# MP3_Breakout.net
KiCad netlist of a schematic drawn in EAGLE
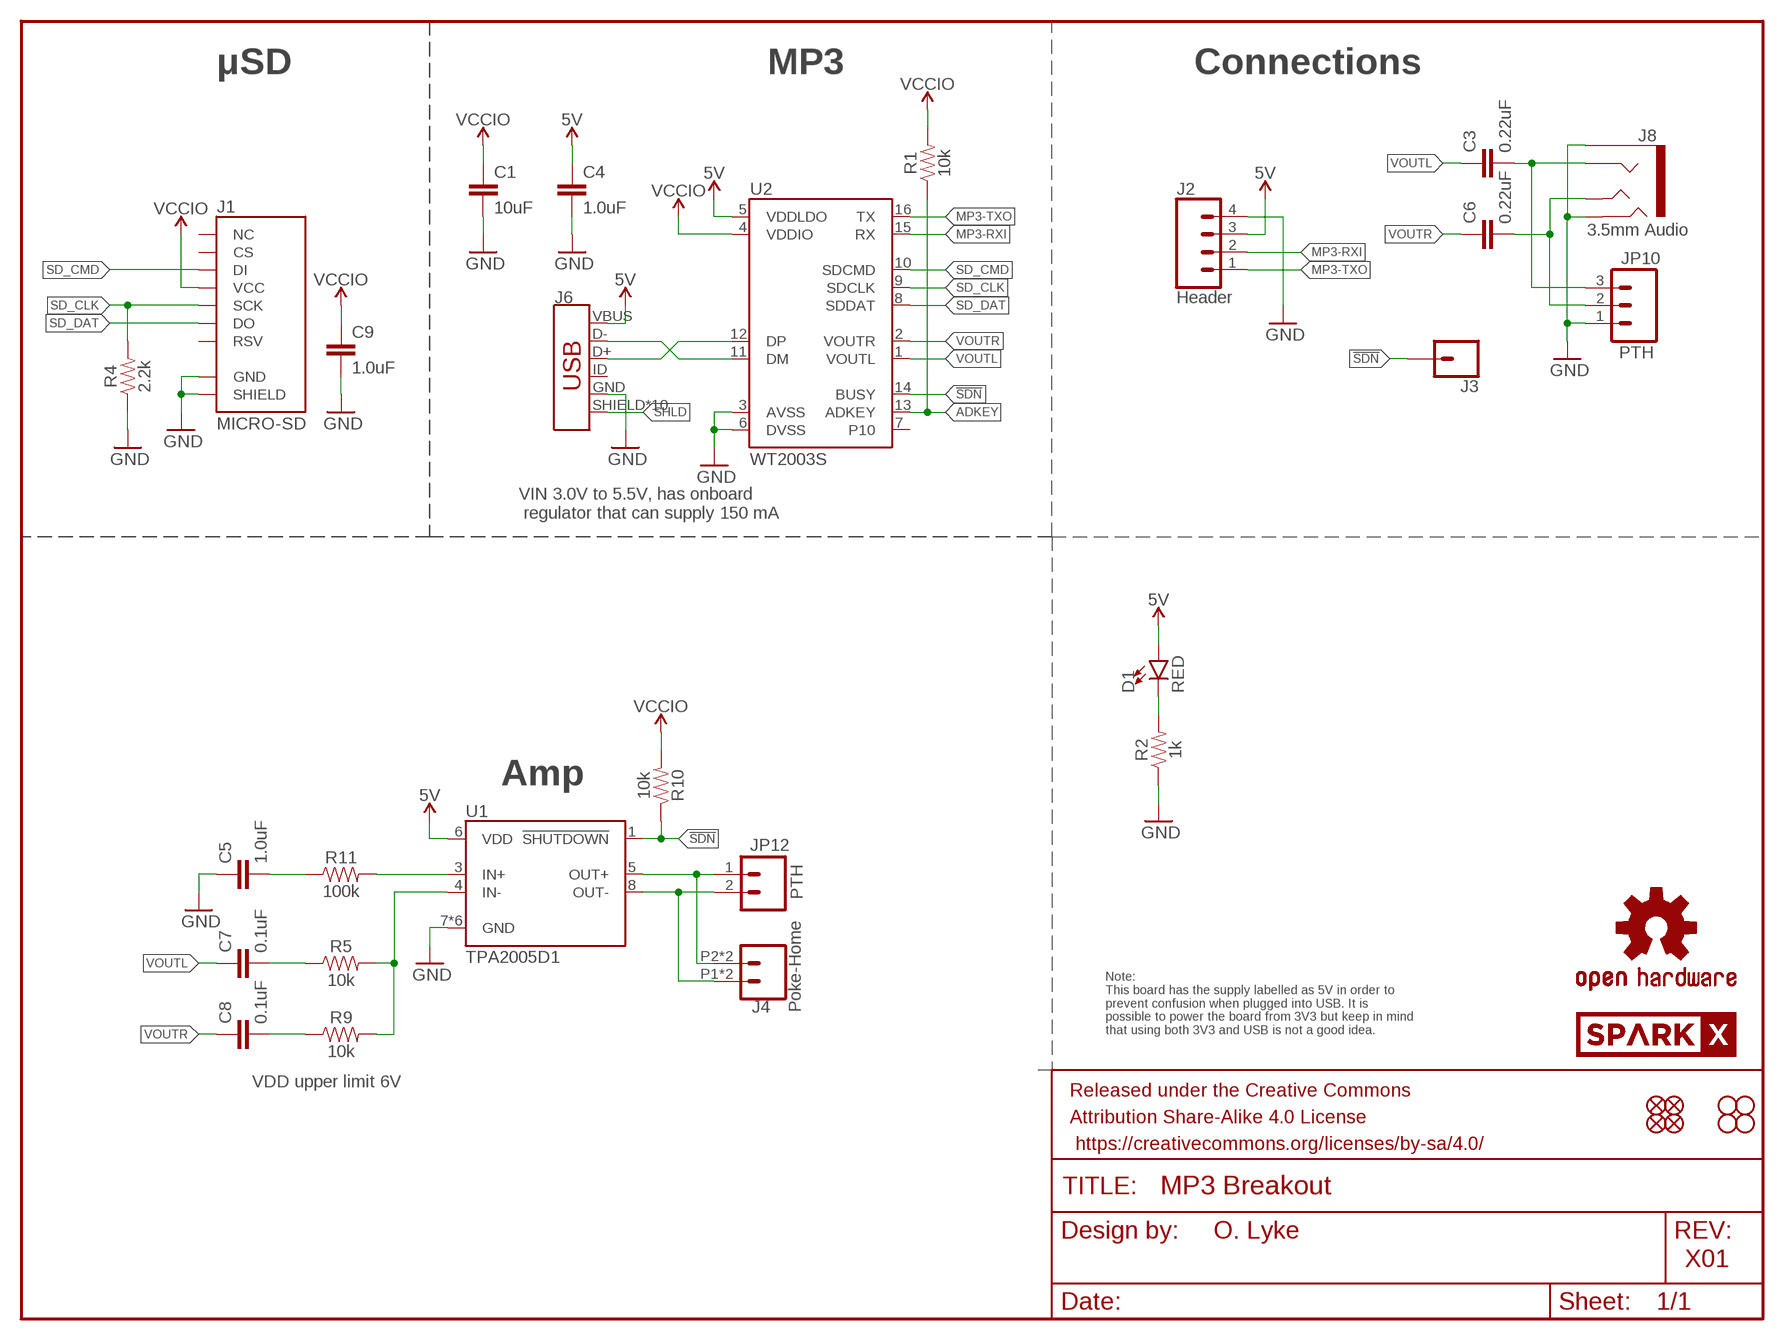
[diagram p0: schematic, sheet 1]

(export (version "E")
  (design (tool "Eeschema 10.0.6"))
  (components
    (comp (ref "C1")
      (value "10uF")
      (footprint "eagle-import:0603")
      (libsource (lib "eagle-import") (part "10UF-0603-6.3V-20%"))
    )
    (comp (ref "C3")
      (value "0.22uF")
      (footprint "eagle-import:0603")
      (libsource (lib "eagle-import") (part "0.22UF-0603-25V-10%"))
    )
    (comp (ref "C4")
      (value "1.0uF")
      (footprint "eagle-import:0603")
      (libsource (lib "eagle-import") (part "1.0UF-0603-16V-10%"))
    )
    (comp (ref "C5")
      (value "1.0uF")
      (footprint "eagle-import:0603")
      (libsource (lib "eagle-import") (part "1.0UF-0603-16V-10%"))
    )
    (comp (ref "C6")
      (value "0.22uF")
      (footprint "eagle-import:0603")
      (libsource (lib "eagle-import") (part "0.22UF-0603-25V-10%"))
    )
    (comp (ref "C7")
      (value "0.1uF")
      (footprint "eagle-import:0603")
      (libsource (lib "eagle-import") (part "0.1UF-0603-25V-(+80/-20%)"))
    )
    (comp (ref "C8")
      (value "0.1uF")
      (footprint "eagle-import:0603")
      (libsource (lib "eagle-import") (part "0.1UF-0603-25V-(+80/-20%)"))
    )
    (comp (ref "C9")
      (value "1.0uF")
      (footprint "eagle-import:0603")
      (libsource (lib "eagle-import") (part "1.0UF-0603-16V-10%"))
    )
    (comp (ref "D1")
      (value "RED")
      (footprint "eagle-import:LED-0603")
      (libsource (lib "eagle-import") (part "LED-RED0603"))
    )
    (comp (ref "FRAME1")
      (value "FRAME-LETTER")
      (footprint "eagle-import:CREATIVE_COMMONS")
      (libsource (lib "eagle-import") (part "FRAME-LETTER"))
    )
    (comp (ref "J1")
      (value "MICRO-SD")
      (footprint "eagle-import:MICRO-SD-SOCKET")
      (libsource (lib "eagle-import") (part "MICRO-SD_CARD_SOCKETPUSH-PUSH"))
    )
    (comp (ref "J2")
      (value "Header")
      (footprint "eagle-import:1X04_NO_SILK")
      (libsource (lib "eagle-import") (part "CONN_041X04_NO_SILK"))
    )
    (comp (ref "J3")
      (value "CONN_01PTH_NO_SILK_YES_STOP")
      (footprint "eagle-import:1X01_NO_SILK")
      (libsource (lib "eagle-import") (part "CONN_01PTH_NO_SILK_YES_STOP"))
    )
    (comp (ref "J4")
      (value "Poke-Home")
      (footprint "eagle-import:1X02_POKEHOME")
      (libsource (lib "eagle-import") (part "CONN_02SMALL_POKEHOME"))
    )
    (comp (ref "J6")
      (value "USB_MICRO-B_HALF_PTH_MILL")
      (footprint "eagle-import:USB-MICROB-PTH-MILL")
      (libsource (lib "eagle-import") (part "USB_MICRO-B_HALF_PTH_MILL"))
    )
    (comp (ref "J8")
      (value "3.5mm Audio")
      (footprint "eagle-import:AUDIO_JACK_3.5MM_TRRS_SMD_RA")
      (libsource (lib "eagle-import") (part "AUDIO_JACK_TRRSSMD_RA"))
    )
    (comp (ref "JP1")
      (value "FIDUCIALUFIDUCIAL")
      (footprint "eagle-import:MICRO-FIDUCIAL")
      (libsource (lib "eagle-import") (part "FIDUCIALUFIDUCIAL"))
    )
    (comp (ref "JP2")
      (value "FIDUCIALUFIDUCIAL")
      (footprint "eagle-import:MICRO-FIDUCIAL")
      (libsource (lib "eagle-import") (part "FIDUCIALUFIDUCIAL"))
    )
    (comp (ref "JP3")
      (value "STAND-OFF")
      (footprint "eagle-import:STAND-OFF")
      (libsource (lib "eagle-import") (part "STAND-OFF"))
    )
    (comp (ref "JP4")
      (value "STAND-OFF")
      (footprint "eagle-import:STAND-OFF")
      (libsource (lib "eagle-import") (part "STAND-OFF"))
    )
    (comp (ref "JP5")
      (value "FIDUCIALUFIDUCIAL")
      (footprint "eagle-import:MICRO-FIDUCIAL")
      (libsource (lib "eagle-import") (part "FIDUCIALUFIDUCIAL"))
    )
    (comp (ref "JP6")
      (value "FIDUCIALUFIDUCIAL")
      (footprint "eagle-import:MICRO-FIDUCIAL")
      (libsource (lib "eagle-import") (part "FIDUCIALUFIDUCIAL"))
    )
    (comp (ref "JP10")
      (value "PTH")
      (footprint "eagle-import:1X03_NO_SILK")
      (libsource (lib "eagle-import") (part "CONN_031X03_NO_SILK"))
    )
    (comp (ref "JP11")
      (value "STAND-OFF")
      (footprint "eagle-import:STAND-OFF")
      (libsource (lib "eagle-import") (part "STAND-OFF"))
    )
    (comp (ref "JP12")
      (value "PTH")
      (footprint "eagle-import:1X02_NO_SILK")
      (libsource (lib "eagle-import") (part "CONN_021X02_NO_SILK"))
    )
    (comp (ref "JP13")
      (value "STAND-OFF")
      (footprint "eagle-import:STAND-OFF")
      (libsource (lib "eagle-import") (part "STAND-OFF"))
    )
    (comp (ref "LOGO1")
      (value "OSHW-LOGOMINI")
      (footprint "eagle-import:OSHW-LOGO-MINI")
      (libsource (lib "eagle-import") (part "OSHW-LOGOMINI"))
    )
    (comp (ref "R1")
      (value "10k")
      (footprint "eagle-import:0603")
      (libsource (lib "eagle-import") (part "10KOHM-0603-1/10W-1%"))
    )
    (comp (ref "R2")
      (value "1k")
      (footprint "eagle-import:0603")
      (libsource (lib "eagle-import") (part "1KOHM-0603-1/10W-1%"))
    )
    (comp (ref "R4")
      (value "2.2k")
      (footprint "eagle-import:0603")
      (libsource (lib "eagle-import") (part "2.2KOHM-0603-1/10W-1%"))
    )
    (comp (ref "R5")
      (value "10k")
      (footprint "eagle-import:0603")
      (libsource (lib "eagle-import") (part "10KOHM-0603-1/10W-1%"))
    )
    (comp (ref "R9")
      (value "10k")
      (footprint "eagle-import:0603")
      (libsource (lib "eagle-import") (part "10KOHM-0603-1/10W-1%"))
    )
    (comp (ref "R10")
      (value "10k")
      (footprint "eagle-import:0603")
      (libsource (lib "eagle-import") (part "10KOHM-0603-1/10W-1%"))
    )
    (comp (ref "R11")
      (value "100k")
      (footprint "eagle-import:0603")
      (libsource (lib "eagle-import") (part "100KOHM-0603-1/10W-1%"))
    )
    (comp (ref "U$2")
      (value "SPARKX-LOGO4")
      (footprint "eagle-import:SPARKX-MEDIUM")
      (libsource (lib "eagle-import") (part "SPARKX-LOGO4"))
    )
    (comp (ref "U1")
      (value "TPA2005D1")
      (footprint "eagle-import:QFN-8_PAD")
      (libsource (lib "eagle-import") (part "TPA2005D1DRB"))
    )
    (comp (ref "U2")
      (value "WT2003S")
      (footprint "eagle-import:SO16")
      (libsource (lib "eagle-import") (part "WT2003S"))
    )
  )
  (nets
    (net (code "1") (name "/~{SDN}") (class "Default")
      (node (ref "J3") (pin "1") (pinfunction "1_1") (pintype "passive"))
      (node (ref "R10") (pin "1") (pinfunction "1_1") (pintype "passive"))
      (node (ref "U1") (pin "1") (pinfunction "~{SHUTDOWN}_1") (pintype "input"))
      (node (ref "U2") (pin "14") (pinfunction "BUSY_14") (pintype "bidirectional"))
    )
    (net (code "2") (name "5V") (class "Default")
      (node (ref "C4") (pin "1") (pinfunction "1_1") (pintype "passive"))
      (node (ref "D1") (pin "A") (pinfunction "A_A") (pintype "passive"))
      (node (ref "J2") (pin "3") (pinfunction "3_3") (pintype "passive"))
      (node (ref "J6") (pin "VBUS") (pinfunction "VBUS_VBUS") (pintype "power_in"))
      (node (ref "U1") (pin "6") (pinfunction "VDD_6") (pintype "power_in"))
      (node (ref "U2") (pin "5") (pinfunction "VDDLDO_5") (pintype "bidirectional"))
    )
    (net (code "3") (name "ADKEY") (class "Default")
      (node (ref "R1") (pin "1") (pinfunction "1_1") (pintype "passive"))
      (node (ref "U2") (pin "13") (pinfunction "ADKEY_13") (pintype "bidirectional"))
    )
    (net (code "4") (name "GND") (class "Default")
      (node (ref "C1") (pin "2") (pinfunction "2_2") (pintype "passive"))
      (node (ref "C4") (pin "2") (pinfunction "2_2") (pintype "passive"))
      (node (ref "C5") (pin "1") (pinfunction "1_1") (pintype "passive"))
      (node (ref "C9") (pin "2") (pinfunction "2_2") (pintype "passive"))
      (node (ref "J1") (pin "CD1") (pinfunction "SHIELD_CD1") (pintype "bidirectional"))
      (node (ref "J1") (pin "GND") (pinfunction "GND_GND") (pintype "bidirectional"))
      (node (ref "J2") (pin "4") (pinfunction "4_4") (pintype "passive"))
      (node (ref "J6") (pin "GND") (pinfunction "GND_GND") (pintype "power_in"))
      (node (ref "J8") (pin "EARTH") (pinfunction "EARTH_EARTH") (pintype "bidirectional"))
      (node (ref "J8") (pin "RING2") (pinfunction "RING2_RING2") (pintype "bidirectional"))
      (node (ref "JP10") (pin "1") (pinfunction "1_1") (pintype "passive"))
      (node (ref "R2") (pin "1") (pinfunction "1_1") (pintype "passive"))
      (node (ref "R4") (pin "1") (pinfunction "1_1") (pintype "passive"))
      (node (ref "U1") (pin "10") (pinfunction "GND_10") (pintype "power_in"))
      (node (ref "U1") (pin "11") (pinfunction "GND_11") (pintype "power_in"))
      (node (ref "U1") (pin "12") (pinfunction "GND_12") (pintype "power_in"))
      (node (ref "U1") (pin "13") (pinfunction "GND_13") (pintype "power_in"))
      (node (ref "U1") (pin "7") (pinfunction "GND_7") (pintype "power_in"))
      (node (ref "U1") (pin "9") (pinfunction "GND_9") (pintype "power_in"))
      (node (ref "U2") (pin "3") (pinfunction "AVSS_3") (pintype "bidirectional"))
      (node (ref "U2") (pin "6") (pinfunction "DVSS_6") (pintype "bidirectional"))
    )
    (net (code "5") (name "MP3-RXI") (class "Default")
      (node (ref "J2") (pin "2") (pinfunction "2_2") (pintype "passive"))
      (node (ref "U2") (pin "15") (pinfunction "RX_15") (pintype "bidirectional"))
    )
    (net (code "6") (name "MP3-TXO") (class "Default")
      (node (ref "J2") (pin "1") (pinfunction "1_1") (pintype "passive"))
      (node (ref "U2") (pin "16") (pinfunction "TX_16") (pintype "bidirectional"))
    )
    (net (code "7") (name "Net-(C3-Pad2)") (class "Default")
      (node (ref "C3") (pin "2") (pinfunction "2_2") (pintype "passive"))
      (node (ref "J8") (pin "RING1") (pinfunction "RING1_RING1") (pintype "bidirectional"))
      (node (ref "JP10") (pin "3") (pinfunction "3_3") (pintype "passive"))
    )
    (net (code "8") (name "Net-(C5-Pad2)") (class "Default")
      (node (ref "C5") (pin "2") (pinfunction "2_2") (pintype "passive"))
      (node (ref "R11") (pin "1") (pinfunction "1_1") (pintype "passive"))
    )
    (net (code "9") (name "Net-(C6-Pad2)") (class "Default")
      (node (ref "C6") (pin "2") (pinfunction "2_2") (pintype "passive"))
      (node (ref "J8") (pin "TIP") (pinfunction "TIP_TIP") (pintype "bidirectional"))
      (node (ref "JP10") (pin "2") (pinfunction "2_2") (pintype "passive"))
    )
    (net (code "10") (name "Net-(C7-Pad2)") (class "Default")
      (node (ref "C7") (pin "2") (pinfunction "2_2") (pintype "passive"))
      (node (ref "R5") (pin "1") (pinfunction "1_1") (pintype "passive"))
    )
    (net (code "11") (name "Net-(C8-Pad2)") (class "Default")
      (node (ref "C8") (pin "2") (pinfunction "2_2") (pintype "passive"))
      (node (ref "R9") (pin "1") (pinfunction "1_1") (pintype "passive"))
    )
    (net (code "12") (name "Net-(D1-PadC)") (class "Default")
      (node (ref "D1") (pin "C") (pinfunction "C_C") (pintype "passive"))
      (node (ref "R2") (pin "2") (pinfunction "2_2") (pintype "passive"))
    )
    (net (code "13") (name "Net-(U1-IN+)") (class "Default")
      (node (ref "R11") (pin "2") (pinfunction "2_2") (pintype "passive"))
      (node (ref "U1") (pin "3") (pinfunction "IN+_3") (pintype "bidirectional"))
    )
    (net (code "14") (name "Net-(U1-IN-)") (class "Default")
      (node (ref "R5") (pin "2") (pinfunction "2_2") (pintype "passive"))
      (node (ref "R9") (pin "2") (pinfunction "2_2") (pintype "passive"))
      (node (ref "U1") (pin "4") (pinfunction "IN-_4") (pintype "bidirectional"))
    )
    (net (code "15") (name "Net-(U1-OUT+)") (class "Default")
      (node (ref "J4") (pin "P2") (pinfunction "2_P2") (pintype "passive"))
      (node (ref "J4") (pin "P4") (pinfunction "2_P4") (pintype "passive"))
      (node (ref "JP12") (pin "1") (pinfunction "1_1") (pintype "passive"))
      (node (ref "U1") (pin "5") (pinfunction "OUT+_5") (pintype "bidirectional"))
    )
    (net (code "16") (name "Net-(U1-OUT-)") (class "Default")
      (node (ref "J4") (pin "P1") (pinfunction "1_P1") (pintype "passive"))
      (node (ref "J4") (pin "P3") (pinfunction "1_P3") (pintype "passive"))
      (node (ref "JP12") (pin "2") (pinfunction "2_2") (pintype "passive"))
      (node (ref "U1") (pin "8") (pinfunction "OUT-_8") (pintype "bidirectional"))
    )
    (net (code "17") (name "Net-(U2-DM)") (class "Default")
      (node (ref "J6") (pin "D-") (pinfunction "D-_D-") (pintype "bidirectional"))
      (node (ref "U2") (pin "11") (pinfunction "DM_11") (pintype "bidirectional"))
    )
    (net (code "18") (name "Net-(U2-DP)") (class "Default")
      (node (ref "J6") (pin "D+") (pinfunction "D+_D+") (pintype "bidirectional"))
      (node (ref "U2") (pin "12") (pinfunction "DP_12") (pintype "bidirectional"))
    )
    (net (code "19") (name "SD_CLK") (class "Default")
      (node (ref "J1") (pin "SCLK") (pinfunction "SCK_SCLK") (pintype "bidirectional"))
      (node (ref "R4") (pin "2") (pinfunction "2_2") (pintype "passive"))
      (node (ref "U2") (pin "9") (pinfunction "SDCLK_9") (pintype "bidirectional"))
    )
    (net (code "20") (name "SD_CMD") (class "Default")
      (node (ref "J1") (pin "DI") (pinfunction "DI_DI") (pintype "bidirectional"))
      (node (ref "U2") (pin "10") (pinfunction "SDCMD_10") (pintype "bidirectional"))
    )
    (net (code "21") (name "SD_DAT") (class "Default")
      (node (ref "J1") (pin "DO") (pinfunction "DO_DO") (pintype "bidirectional"))
      (node (ref "U2") (pin "8") (pinfunction "SDDAT_8") (pintype "bidirectional"))
    )
    (net (code "22") (name "SHLD") (class "Default")
      (node (ref "J6") (pin "SHIELD") (pinfunction "SHIELD_SHIELD") (pintype "bidirectional"))
      (node (ref "J6") (pin "SHIELD10") (pinfunction "SHIELD_SHIELD10") (pintype "bidirectional"))
      (node (ref "J6") (pin "SHIELD2") (pinfunction "SHIELD_SHIELD2") (pintype "bidirectional"))
      (node (ref "J6") (pin "SHIELD3") (pinfunction "SHIELD_SHIELD3") (pintype "bidirectional"))
      (node (ref "J6") (pin "SHIELD4") (pinfunction "SHIELD_SHIELD4") (pintype "bidirectional"))
      (node (ref "J6") (pin "SHIELD5") (pinfunction "SHIELD_SHIELD5") (pintype "bidirectional"))
      (node (ref "J6") (pin "SHIELD6") (pinfunction "SHIELD_SHIELD6") (pintype "bidirectional"))
      (node (ref "J6") (pin "SHIELD7") (pinfunction "SHIELD_SHIELD7") (pintype "bidirectional"))
      (node (ref "J6") (pin "SHIELD8") (pinfunction "SHIELD_SHIELD8") (pintype "bidirectional"))
      (node (ref "J6") (pin "SHIELD9") (pinfunction "SHIELD_SHIELD9") (pintype "bidirectional"))
    )
    (net (code "23") (name "VCCIO") (class "Default")
      (node (ref "C1") (pin "1") (pinfunction "1_1") (pintype "passive"))
      (node (ref "C9") (pin "1") (pinfunction "1_1") (pintype "passive"))
      (node (ref "J1") (pin "VCC") (pinfunction "VCC_VCC") (pintype "bidirectional"))
      (node (ref "R1") (pin "2") (pinfunction "2_2") (pintype "passive"))
      (node (ref "R10") (pin "2") (pinfunction "2_2") (pintype "passive"))
      (node (ref "U2") (pin "4") (pinfunction "VDDIO_4") (pintype "bidirectional"))
    )
    (net (code "24") (name "VOUTL") (class "Default")
      (node (ref "C3") (pin "1") (pinfunction "1_1") (pintype "passive"))
      (node (ref "C7") (pin "1") (pinfunction "1_1") (pintype "passive"))
      (node (ref "U2") (pin "1") (pinfunction "VOUTL_1") (pintype "bidirectional"))
    )
    (net (code "25") (name "VOUTR") (class "Default")
      (node (ref "C6") (pin "1") (pinfunction "1_1") (pintype "passive"))
      (node (ref "C8") (pin "1") (pinfunction "1_1") (pintype "passive"))
      (node (ref "U2") (pin "2") (pinfunction "VOUTR_2") (pintype "bidirectional"))
    )
    (net (code "26") (name "unconnected-(J1-NC-PadRSV2)") (class "Default")
      (node (ref "J1") (pin "RSV2") (pinfunction "NC_RSV2") (pintype "bidirectional"))
    )
    (net (code "27") (name "unconnected-(J1-PadCS)") (class "Default")
      (node (ref "J1") (pin "CS") (pinfunction "CS_CS") (pintype "bidirectional"))
    )
    (net (code "28") (name "unconnected-(J1-RSV-PadRSV1)") (class "Default")
      (node (ref "J1") (pin "RSV1") (pinfunction "RSV_RSV1") (pintype "bidirectional"))
    )
    (net (code "29") (name "unconnected-(J6-PadID)") (class "Default")
      (node (ref "J6") (pin "ID") (pinfunction "ID_ID") (pintype "bidirectional"))
    )
    (net (code "30") (name "unconnected-(U2-P10-Pad7)") (class "Default")
      (node (ref "U2") (pin "7") (pinfunction "P10_7") (pintype "bidirectional"))
    )
  )
)
